# BD4Gv1.net
KiCad netlist of a schematic drawn in Altium Designer
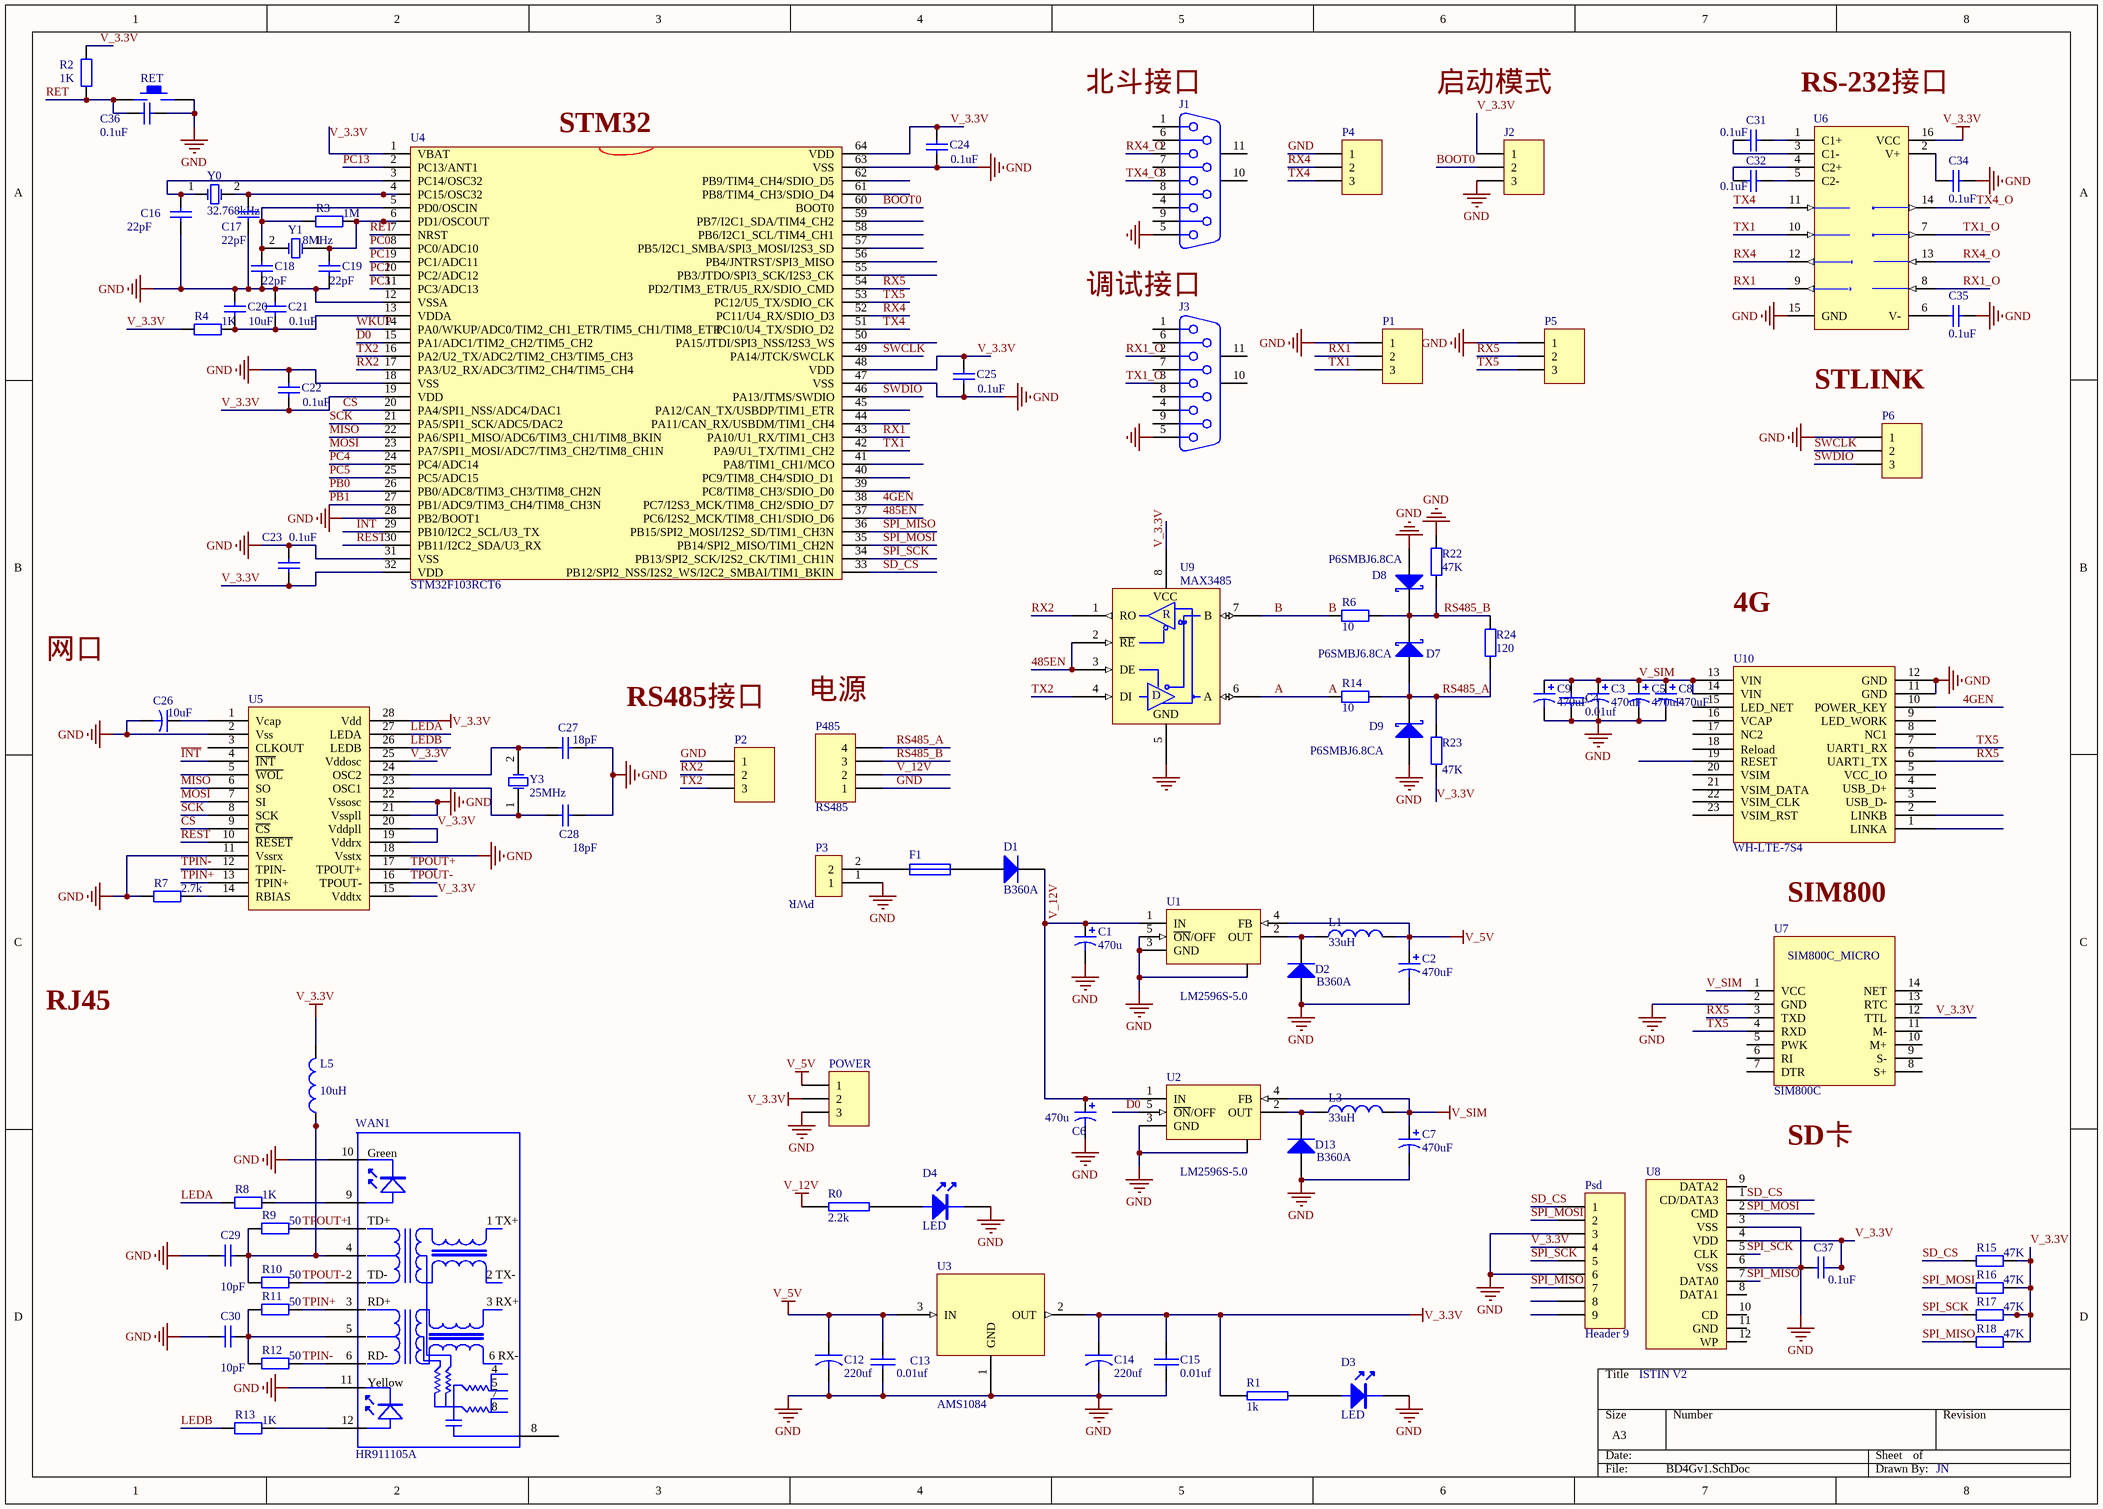
[diagram p0: BD4Gv1.SchDoc]

(export (version "E")
  (design (tool "Eeschema 10.0.6"))
  (components
    (comp (ref "C1")
      (value "470u")
      (footprint "C1007")
      (description "Polarized Capacitor (Surface Mount)")
      (fields (field (name "Comment") "470u/35V"))
      (libsource (lib "Miscellaneous Devices") (part "Cap Pol3"))
    )
    (comp (ref "C2")
      (value "470uF")
      (footprint "SMC")
      (description "Polarized Capacitor (Surface Mount)")
      (fields (field (name "Comment") "470u/10V"))
      (libsource (lib "Miscellaneous Devices") (part "Cap Pol3"))
    )
    (comp (ref "C3")
      (value "470uF")
      (footprint "SMC")
      (description "Polarized Capacitor (Surface Mount)")
      (fields (field (name "Comment") "470u/10V"))
      (libsource (lib "Miscellaneous Devices") (part "Cap Pol3"))
    )
    (comp (ref "C4")
      (value "0.01uf")
      (footprint "0805")
      (description "Capacitor")
      (libsource (lib "*") (part "CAP"))
    )
    (comp (ref "C5")
      (value "470uF")
      (footprint "SMC")
      (description "Polarized Capacitor (Surface Mount)")
      (fields (field (name "Comment") "470u/10V"))
      (libsource (lib "Miscellaneous Devices") (part "Cap Pol3"))
    )
    (comp (ref "C6")
      (value "470u")
      (footprint "C1007")
      (description "Polarized Capacitor (Surface Mount)")
      (fields (field (name "Comment") "470u/35V"))
      (libsource (lib "Miscellaneous Devices") (part "Cap Pol3"))
    )
    (comp (ref "C7")
      (value "470uF")
      (footprint "SMC")
      (description "Polarized Capacitor (Surface Mount)")
      (fields (field (name "Comment") "470u/10V"))
      (libsource (lib "Miscellaneous Devices") (part "Cap Pol3"))
    )
    (comp (ref "C8")
      (value "470uF")
      (footprint "SMC")
      (description "Polarized Capacitor (Surface Mount)")
      (fields (field (name "Comment") "470u/10V"))
      (libsource (lib "Miscellaneous Devices") (part "Cap Pol3"))
    )
    (comp (ref "C9")
      (value "470uF")
      (footprint "CC6.56.5")
      (description "Polarized Capacitor (Surface Mount)")
      (fields (field (name "Comment") "470u/10V"))
      (libsource (lib "Miscellaneous Devices") (part "Cap Pol3"))
    )
    (comp (ref "C12")
      (value "220uf")
      (footprint "SMC")
      (description "Capacitor")
      (libsource (lib "*") (part "CAPACITOR"))
    )
    (comp (ref "C13")
      (value "0.01uf")
      (footprint "0805")
      (description "Capacitor")
      (libsource (lib "*") (part "CAP"))
    )
    (comp (ref "C14")
      (value "220uf")
      (footprint "SMC")
      (description "Capacitor")
      (libsource (lib "*") (part "CAPACITOR"))
    )
    (comp (ref "C15")
      (value "0.01uf")
      (footprint "0805")
      (description "Capacitor")
      (libsource (lib "*") (part "CAP"))
    )
    (comp (ref "C16")
      (value "22pF")
      (footprint "0805")
      (description "Capacitor")
      (libsource (lib "Miscellaneous Devices") (part "Cap"))
    )
    (comp (ref "C17")
      (value "22pF")
      (footprint "0805")
      (description "Capacitor")
      (libsource (lib "Miscellaneous Devices") (part "Cap"))
    )
    (comp (ref "C18")
      (value "22pF")
      (footprint "0805")
      (description "Capacitor")
      (libsource (lib "Miscellaneous Devices") (part "Cap"))
    )
    (comp (ref "C19")
      (value "22pF")
      (footprint "0805")
      (description "Capacitor")
      (libsource (lib "Miscellaneous Devices") (part "Cap"))
    )
    (comp (ref "C20")
      (value "10uF")
      (footprint "0805")
      (description "Capacitor")
      (libsource (lib "Miscellaneous Devices") (part "Cap"))
    )
    (comp (ref "C21")
      (value "0.1uF")
      (footprint "0805")
      (description "Capacitor")
      (libsource (lib "Miscellaneous Devices") (part "Cap"))
    )
    (comp (ref "C22")
      (value "0.1uF")
      (footprint "0805")
      (description "Capacitor")
      (libsource (lib "Miscellaneous Devices") (part "Cap"))
    )
    (comp (ref "C23")
      (value "0.1uF")
      (footprint "0805")
      (description "Capacitor")
      (libsource (lib "Miscellaneous Devices") (part "Cap"))
    )
    (comp (ref "C24")
      (value "0.1uF")
      (footprint "0805")
      (description "Capacitor")
      (libsource (lib "Miscellaneous Devices") (part "Cap"))
    )
    (comp (ref "C25")
      (value "0.1uF")
      (footprint "0805")
      (description "Capacitor")
      (libsource (lib "Miscellaneous Devices") (part "Cap"))
    )
    (comp (ref "C26")
      (value "10uF")
      (footprint "0805")
      (description "Capacitor")
      (libsource (lib "Miscellaneous Devices") (part "Cap2"))
    )
    (comp (ref "C27")
      (value "18pF")
      (footprint "0805")
      (description "Capacitor")
      (libsource (lib "Miscellaneous Devices") (part "Cap"))
    )
    (comp (ref "C28")
      (value "18pF")
      (footprint "0805")
      (description "Capacitor")
      (libsource (lib "Miscellaneous Devices") (part "Cap"))
    )
    (comp (ref "C29")
      (value "10pF")
      (footprint "0805")
      (description "Capacitor")
      (libsource (lib "Miscellaneous Devices") (part "Cap"))
    )
    (comp (ref "C30")
      (value "10pF")
      (footprint "0805")
      (description "Capacitor")
      (libsource (lib "Miscellaneous Devices") (part "Cap"))
    )
    (comp (ref "C31")
      (value "0.1uF")
      (footprint "0805")
      (description "Capacitor")
      (libsource (lib "HLK-RM04_KIT-V2.3") (part "Cap"))
    )
    (comp (ref "C32")
      (value "0.1uF")
      (footprint "0805")
      (description "Capacitor")
      (libsource (lib "HLK-RM04_KIT-V2.3") (part "Cap"))
    )
    (comp (ref "C34")
      (value "0.1uF")
      (footprint "0805")
      (description "Capacitor")
      (libsource (lib "HLK-RM04_KIT-V2.3") (part "Cap"))
    )
    (comp (ref "C35")
      (value "0.1uF")
      (footprint "0805")
      (description "Capacitor")
      (libsource (lib "HLK-RM04_KIT-V2.3") (part "Cap"))
    )
    (comp (ref "C36")
      (value "0.1uF")
      (footprint "0805")
      (description "Capacitor")
      (libsource (lib "Miscellaneous Devices") (part "Cap"))
    )
    (comp (ref "C37")
      (value "0.1uF")
      (footprint "0805")
      (description "Capacitor")
      (libsource (lib "Miscellaneous Devices") (part "Cap"))
    )
    (comp (ref "D1")
      (value "B360A")
      (footprint "B360A")
      (description "Default Diode")
      (libsource (lib "Miscellaneous Devices") (part "Diode"))
    )
    (comp (ref "D2")
      (value "B360A")
      (footprint "B360A")
      (description "Default Diode")
      (libsource (lib "Miscellaneous Devices") (part "Diode"))
    )
    (comp (ref "D3") (value "LED") (footprint "LED_side") (libsource (lib "*") (part "LED")))
    (comp (ref "D4") (value "LED") (footprint "LED_side") (libsource (lib "*") (part "LED")))
    (comp (ref "D7")
      (value "P6SMBJ6.8CA")
      (footprint "DO-2144AA")
      (description "Schottky Diode")
      (libsource (lib "Miscellaneous Devices") (part "D Schottky"))
    )
    (comp (ref "D8")
      (value "P6SMBJ6.8CA")
      (footprint "DO-2144AA")
      (description "Schottky Diode")
      (libsource (lib "Miscellaneous Devices") (part "D Schottky"))
    )
    (comp (ref "D9")
      (value "P6SMBJ6.8CA")
      (footprint "DO-2144AA")
      (description "Schottky Diode")
      (libsource (lib "Miscellaneous Devices") (part "D Schottky"))
    )
    (comp (ref "D13")
      (value "B360A")
      (footprint "B360A")
      (description "Default Diode")
      (libsource (lib "Miscellaneous Devices") (part "Diode"))
    )
    (comp (ref "F1")
      (value "保险丝")
      (footprint "1812")
      (description "Fuse")
      (libsource (lib "Miscellaneous Devices") (part "Fuse 1"))
    )
    (comp (ref "J1")
      (value "D Connector 9")
      (footprint "DB9P")
      (description "Receptacle Assembly, 9 Position, Right Angle")
      (libsource (lib "Miscellaneous Connectors") (part "D Connector 9"))
    )
    (comp (ref "J2")
      (value "boot")
      (footprint "HDR1X3")
      (description "Header, 3-Pin")
      (libsource (lib "hete") (part "Header 3"))
    )
    (comp (ref "J3")
      (value "D Connector 9")
      (footprint "DB9P")
      (description "Receptacle Assembly, 9 Position, Right Angle")
      (libsource (lib "Miscellaneous Connectors") (part "D Connector 9"))
    )
    (comp (ref "L1")
      (value "33uH")
      (footprint "L0630")
      (description "Inductor,3A")
      (libsource (lib "Miscellaneous Devices") (part "Inductor"))
    )
    (comp (ref "L3")
      (value "33uH")
      (footprint "L0630")
      (description "Inductor,3A")
      (libsource (lib "Miscellaneous Devices") (part "Inductor"))
    )
    (comp (ref "L5")
      (value "10uH")
      (footprint "0805")
      (description "Inductor")
      (libsource (lib "Miscellaneous Devices") (part "Inductor"))
    )
    (comp (ref "P1")
      (value "UART")
      (footprint "HDR1X3")
      (description "Header, 3-Pin")
      (libsource (lib "Miscellaneous Connectors") (part "Header 3"))
    )
    (comp (ref "P2")
      (value "BD-TEST")
      (footprint "HDR1X3")
      (description "Header, 3-Pin")
      (libsource (lib "Miscellaneous Connectors") (part "MHDR1X3"))
    )
    (comp (ref "P3") (value "~") (footprint "H2_5.08_side") (libsource (lib "BD") (part "PWR")))
    (comp (ref "P4")
      (value "BD-TEST")
      (footprint "HDR1X3")
      (description "Header, 3-Pin")
      (libsource (lib "Miscellaneous Connectors") (part "MHDR1X3"))
    )
    (comp (ref "P5")
      (value "UART")
      (footprint "HDR1X3")
      (description "Header, 3-Pin")
      (libsource (lib "Miscellaneous Connectors") (part "Header 3"))
    )
    (comp (ref "P6")
      (value "STLINK")
      (footprint "HDR1X3")
      (description "Header, 3-Pin")
      (libsource (lib "Miscellaneous Connectors") (part "Header 3"))
    )
    (comp (ref "P485")
      (value "RS485")
      (footprint "H4_3.81")
      (description "Header, 4-Pin")
      (libsource (lib "Miscellaneous Connectors") (part "Header 4"))
    )
    (comp (ref "POWER")
      (value "UART")
      (footprint "HDR1X3")
      (description "Header, 3-Pin")
      (libsource (lib "Miscellaneous Connectors") (part "Header 3"))
    )
    (comp (ref "Psd")
      (value "Header 9")
      (footprint "HDR1X9")
      (description "Header, 9-Pin")
      (libsource (lib "Miscellaneous Connectors") (part "Header 9"))
    )
    (comp (ref "R0") (value "2.2k") (footprint "0805") (libsource (lib "*") (part "RES2")))
    (comp (ref "R1") (value "1k") (footprint "0805") (libsource (lib "*") (part "RES2")))
    (comp (ref "R2")
      (value "1K")
      (footprint "0805")
      (description "Resistor")
      (fields (field (name "Comment") "1k"))
      (libsource (lib "") (part "Res2_2"))
    )
    (comp (ref "R3")
      (value "1M")
      (footprint "0805")
      (description "Resistor")
      (libsource (lib "Miscellaneous Devices") (part "Res2"))
    )
    (comp (ref "R4")
      (value "1K")
      (footprint "0805")
      (description "Resistor")
      (fields (field (name "Comment") "1k"))
      (libsource (lib "Miscellaneous Devices") (part "Res2"))
    )
    (comp (ref "R6")
      (value "10")
      (footprint "0805")
      (description "Resistor")
      (libsource (lib "Miscellaneous Devices") (part "Res2"))
    )
    (comp (ref "R7")
      (value "2.7k")
      (footprint "0805")
      (description "Resistor")
      (libsource (lib "Miscellaneous Devices") (part "Res2"))
    )
    (comp (ref "R8")
      (value "1K")
      (footprint "0805")
      (description "Resistor")
      (fields (field (name "Comment") "1k"))
      (libsource (lib "Miscellaneous Devices") (part "Res2"))
    )
    (comp (ref "R9")
      (value "50")
      (footprint "0805")
      (description "Resistor")
      (libsource (lib "Miscellaneous Devices") (part "Res2"))
    )
    (comp (ref "R10")
      (value "50")
      (footprint "0805")
      (description "Resistor")
      (libsource (lib "Miscellaneous Devices") (part "Res2"))
    )
    (comp (ref "R11")
      (value "50")
      (footprint "0805")
      (description "Resistor")
      (libsource (lib "Miscellaneous Devices") (part "Res2"))
    )
    (comp (ref "R12")
      (value "50")
      (footprint "0805")
      (description "Resistor")
      (libsource (lib "Miscellaneous Devices") (part "Res2"))
    )
    (comp (ref "R13")
      (value "1K")
      (footprint "0805")
      (description "Resistor")
      (fields (field (name "Comment") "1k"))
      (libsource (lib "Miscellaneous Devices") (part "Res2"))
    )
    (comp (ref "R14")
      (value "10")
      (footprint "0805")
      (description "Resistor")
      (libsource (lib "Miscellaneous Devices") (part "Res2"))
    )
    (comp (ref "R15")
      (value "47K")
      (footprint "0805")
      (description "Resistor")
      (fields (field (name "Comment") "47k"))
      (libsource (lib "Miscellaneous Devices") (part "Res2"))
    )
    (comp (ref "R16")
      (value "47K")
      (footprint "0805")
      (description "Resistor")
      (fields (field (name "Comment") "47k"))
      (libsource (lib "Miscellaneous Devices") (part "Res2"))
    )
    (comp (ref "R17")
      (value "47K")
      (footprint "0805")
      (description "Resistor")
      (fields (field (name "Comment") "47k"))
      (libsource (lib "Miscellaneous Devices") (part "Res2"))
    )
    (comp (ref "R18")
      (value "47K")
      (footprint "0805")
      (description "Resistor")
      (fields (field (name "Comment") "47k"))
      (libsource (lib "Miscellaneous Devices") (part "Res2"))
    )
    (comp (ref "R22")
      (value "47K")
      (footprint "0805")
      (description "Resistor")
      (libsource (lib "") (part "Res2_1"))
    )
    (comp (ref "R23")
      (value "47K")
      (footprint "0805")
      (description "Resistor")
      (libsource (lib "") (part "Res2_1"))
    )
    (comp (ref "R24")
      (value "120")
      (footprint "0805")
      (description "Resistor")
      (libsource (lib "") (part "Res2_1"))
    )
    (comp (ref "RET") (value "KEY_M") (footprint "KEY_90") (libsource (lib "MiniSTM32底板_SCH") (part "KEY_M")))
    (comp (ref "U1")
      (value "LM2596S-5.0")
      (footprint "936A-02")
      (description "5V稳压芯片")
      (libsource (lib "fszhang") (part "LM2596S-5.0"))
    )
    (comp (ref "U2")
      (value "LM2596S-5.0")
      (footprint "936A-02")
      (description "5V稳压芯片")
      (libsource (lib "fszhang") (part "LM2596S-5.0"))
    )
    (comp (ref "U3") (value "AMS1084") (footprint "TO-252") (libsource (lib "Sheet1") (part "AMS117")))
    (comp (ref "U4")
      (value "STM32F103RCT6")
      (footprint "LQFP64_N")
      (libsource (lib "MiniSTM32 V3.0封装库") (part "STM32F103RDT6"))
    )
    (comp (ref "U5") (value "EN28J60") (footprint "SSOP28") (libsource (lib "PN532") (part "EN28J60")))
    (comp (ref "U6")
      (value "MAX3232ESE")
      (footprint "NSO16_N")
      (description "3.0V TO 5.5V, Low-Power, up to 1Mbps, True RS-232 Transceiver Using Four 0.1µF External Capacitor")
      (libsource (lib "Maxim Communication Transceiver") (part "MAX3232ESE"))
    )
    (comp (ref "U7")
      (value "SIM800C")
      (footprint "PCBComponent_1")
      (libsource (lib "SIM800C_MICRO") (part "Component_1"))
    )
    (comp (ref "U8")
      (value "sd card")
      (footprint "MICRO-SD")
      (libsource (lib "MiniSTM32 V3.0封装库") (part "sd card"))
    )
    (comp (ref "U9") (value "MAX3485") (footprint "NSO8_M") (libsource (lib "*") (part "MAX1487E")))
    (comp (ref "U10")
      (value "WH-LTE-7S4")
      (footprint "WH-LTE-7S4")
      (libsource (lib "BD4Gv1") (part "WH-LTE-7S4"))
    )
    (comp (ref "WAN1")
      (value "HR911105A")
      (footprint "HR911105A")
      (libsource (lib "V2-Project") (part "HR911105A"))
    )
    (comp (ref "Y0")
      (value "32.768kHz")
      (footprint "XTAL-B")
      (description "Crystal Oscillator")
      (libsource (lib "MiniSTM32 V3.0封装库") (part "XTAL"))
    )
    (comp (ref "Y1")
      (value "8MHz")
      (footprint "贴片晶振")
      (description "Crystal Oscillator")
      (libsource (lib "MiniSTM32 V3.0封装库") (part "XTAL"))
    )
    (comp (ref "Y3")
      (value "25MHz")
      (footprint "4P-Crystal")
      (description "Crystal Oscillator")
      (libsource (lib "Miscellaneous Devices") (part "XTAL"))
    )
  )
  (nets
    (net (code "1") (name "/4GEN") (class "Default")
      (node (ref "U10") (pin "10") (pinfunction "POWER_KEY_10") (pintype "passive"))
      (node (ref "U4") (pin "38") (pinfunction "PC7/I2S3_MCK/TIM8_CH2/SDIO_D7_38") (pintype "passive"))
    )
    (net (code "2") (name "/485EN") (class "Default")
      (node (ref "U4") (pin "37") (pinfunction "PC6/I2S2_MCK/TIM8_CH1/SDIO_D6_37") (pintype "passive"))
      (node (ref "U9") (pin "2") (pinfunction "~{RE}_2") (pintype "input"))
      (node (ref "U9") (pin "3") (pinfunction "DE_3") (pintype "input"))
    )
    (net (code "3") (name "/A") (class "Default")
      (node (ref "R14") (pin "1") (pinfunction "1_1") (pintype "passive"))
      (node (ref "U9") (pin "6") (pinfunction "A_6") (pintype "bidirectional"))
    )
    (net (code "4") (name "/B") (class "Default")
      (node (ref "R6") (pin "1") (pinfunction "1_1") (pintype "passive"))
      (node (ref "U9") (pin "7") (pinfunction "B_7") (pintype "bidirectional"))
    )
    (net (code "5") (name "/BOOT0") (class "Default")
      (node (ref "J2") (pin "2") (pinfunction "2_2") (pintype "passive"))
      (node (ref "U4") (pin "60") (pinfunction "BOOT0_60") (pintype "passive"))
    )
    (net (code "6") (name "/D0") (class "Default")
      (node (ref "U2") (pin "5") (pinfunction "~{ON}/OFF_5") (pintype "input"))
      (node (ref "U4") (pin "15") (pinfunction "PA1/ADC1/TIM2_CH2/TIM5_CH2_15") (pintype "passive"))
    )
    (net (code "7") (name "/LEDA") (class "Default")
      (node (ref "R8") (pin "1") (pinfunction "1_1") (pintype "passive"))
      (node (ref "U5") (pin "27") (pinfunction "LEDA_27") (pintype "passive"))
    )
    (net (code "8") (name "/LEDB") (class "Default")
      (node (ref "R13") (pin "1") (pinfunction "1_1") (pintype "passive"))
      (node (ref "U5") (pin "26") (pinfunction "LEDB_26") (pintype "passive"))
    )
    (net (code "9") (name "/MISO") (class "Default")
      (node (ref "U4") (pin "22") (pinfunction "PA6/SPI1_MISO/ADC6/TIM3_CH1/TIM8_BKIN_22") (pintype "passive"))
      (node (ref "U5") (pin "6") (pinfunction "SO_6") (pintype "passive"))
    )
    (net (code "10") (name "/MOSI") (class "Default")
      (node (ref "U4") (pin "23") (pinfunction "PA7/SPI1_MOSI/ADC7/TIM3_CH2/TIM8_CH1N_23") (pintype "passive"))
      (node (ref "U5") (pin "7") (pinfunction "SI_7") (pintype "passive"))
    )
    (net (code "11") (name "/PB0") (class "Default")
      (node (ref "U4") (pin "26") (pinfunction "PB0/ADC8/TIM3_CH3/TIM8_CH2N_26") (pintype "passive"))
    )
    (net (code "12") (name "/PB1") (class "Default")
      (node (ref "U4") (pin "27") (pinfunction "PB1/ADC9/TIM3_CH4/TIM8_CH3N_27") (pintype "passive"))
    )
    (net (code "13") (name "/PC0") (class "Default")
      (node (ref "U4") (pin "8") (pinfunction "PC0/ADC10_8") (pintype "passive"))
    )
    (net (code "14") (name "/PC1") (class "Default")
      (node (ref "U4") (pin "9") (pinfunction "PC1/ADC11_9") (pintype "passive"))
    )
    (net (code "15") (name "/PC2") (class "Default")
      (node (ref "U4") (pin "10") (pinfunction "PC2/ADC12_10") (pintype "passive"))
    )
    (net (code "16") (name "/PC3") (class "Default")
      (node (ref "U4") (pin "11") (pinfunction "PC3/ADC13_11") (pintype "passive"))
    )
    (net (code "17") (name "/PC4") (class "Default")
      (node (ref "U4") (pin "24") (pinfunction "PC4/ADC14_24") (pintype "passive"))
    )
    (net (code "18") (name "/PC5") (class "Default")
      (node (ref "U4") (pin "25") (pinfunction "PC5/ADC15_25") (pintype "passive"))
    )
    (net (code "19") (name "/PC13") (class "Default")
      (node (ref "U4") (pin "2") (pinfunction "PC13/ANT1_2") (pintype "passive"))
    )
    (net (code "20") (name "/REST") (class "Default")
      (node (ref "U4") (pin "30") (pinfunction "PB11/I2C2_SDA/U3_RX_30") (pintype "passive"))
      (node (ref "U5") (pin "10") (pinfunction "~{RESET}_10") (pintype "passive"))
    )
    (net (code "21") (name "/RET") (class "Default")
      (node (ref "C36") (pin "1") (pinfunction "1_1") (pintype "passive"))
      (node (ref "R2") (pin "1") (pinfunction "1_1") (pintype "passive"))
      (node (ref "RET") (pin "1") (pinfunction "1_1") (pintype "passive"))
      (node (ref "U4") (pin "7") (pinfunction "NRST_7") (pintype "passive"))
    )
    (net (code "22") (name "/RS485_A") (class "Default")
      (node (ref "D7") (pin "1") (pinfunction "A_1") (pintype "passive"))
      (node (ref "D9") (pin "2") (pinfunction "K_2") (pintype "passive"))
      (node (ref "P485") (pin "4") (pinfunction "4_4") (pintype "passive"))
      (node (ref "R14") (pin "2") (pinfunction "2_2") (pintype "passive"))
      (node (ref "R23") (pin "1") (pinfunction "1_1") (pintype "passive"))
      (node (ref "R24") (pin "2") (pinfunction "2_2") (pintype "passive"))
    )
    (net (code "23") (name "/RS485_B") (class "Default")
      (node (ref "D7") (pin "2") (pinfunction "K_2") (pintype "passive"))
      (node (ref "D8") (pin "2") (pinfunction "K_2") (pintype "passive"))
      (node (ref "P485") (pin "3") (pinfunction "3_3") (pintype "passive"))
      (node (ref "R22") (pin "2") (pinfunction "2_2") (pintype "passive"))
      (node (ref "R24") (pin "1") (pinfunction "1_1") (pintype "passive"))
      (node (ref "R6") (pin "2") (pinfunction "2_2") (pintype "passive"))
    )
    (net (code "24") (name "/RX1") (class "Default")
      (node (ref "P1") (pin "2") (pinfunction "2_2") (pintype "passive"))
      (node (ref "U4") (pin "43") (pinfunction "PA10/U1_RX/TIM1_CH3_43") (pintype "passive"))
      (node (ref "U6") (pin "9") (pinfunction "R2OUT_9") (pintype "output"))
    )
    (net (code "25") (name "/RX1_O") (class "Default")
      (node (ref "J3") (pin "2") (pinfunction "2_2") (pintype "passive"))
      (node (ref "U6") (pin "8") (pinfunction "R2IN_8") (pintype "input"))
    )
    (net (code "26") (name "/RX2") (class "Default")
      (node (ref "P2") (pin "2") (pinfunction "2_2") (pintype "passive"))
      (node (ref "U4") (pin "17") (pinfunction "PA3/U2_RX/ADC3/TIM2_CH4/TIM5_CH4_17") (pintype "passive"))
      (node (ref "U9") (pin "1") (pinfunction "RO_1") (pintype "output"))
    )
    (net (code "27") (name "/RX4") (class "Default")
      (node (ref "P4") (pin "2") (pinfunction "2_2") (pintype "passive"))
      (node (ref "U4") (pin "52") (pinfunction "PC11/U4_RX/SDIO_D3_52") (pintype "passive"))
      (node (ref "U6") (pin "12") (pinfunction "R1OUT_12") (pintype "output"))
    )
    (net (code "28") (name "/RX4_O") (class "Default")
      (node (ref "J1") (pin "2") (pinfunction "2_2") (pintype "passive"))
      (node (ref "U6") (pin "13") (pinfunction "R1IN_13") (pintype "input"))
    )
    (net (code "29") (name "/RX5") (class "Default")
      (node (ref "P5") (pin "2") (pinfunction "2_2") (pintype "passive"))
      (node (ref "U10") (pin "6") (pinfunction "UART1_TX_6") (pintype "passive"))
      (node (ref "U4") (pin "54") (pinfunction "PD2/TIM3_ETR/U5_RX/SDIO_CMD_54") (pintype "passive"))
      (node (ref "U7") (pin "3") (pinfunction "TXD_3") (pintype "passive"))
    )
    (net (code "30") (name "/SCK") (class "Default")
      (node (ref "U4") (pin "21") (pinfunction "PA5/SPI1_SCK/ADC5/DAC2_21") (pintype "passive"))
      (node (ref "U5") (pin "8") (pinfunction "SCK_8") (pintype "passive"))
    )
    (net (code "31") (name "/SD_CS") (class "Default")
      (node (ref "Psd") (pin "1") (pinfunction "1_1") (pintype "passive"))
      (node (ref "R15") (pin "1") (pinfunction "1_1") (pintype "passive"))
      (node (ref "U4") (pin "33") (pinfunction "PB12/SPI2_NSS/I2S2_WS/I2C2_SMBAI/TIM1_BKIN_33") (pintype "passive"))
      (node (ref "U8") (pin "1") (pinfunction "CD/DATA3_1") (pintype "passive"))
    )
    (net (code "34") (name "/SPI_MISO") (class "Default")
      (node (ref "Psd") (pin "7") (pinfunction "7_7") (pintype "passive"))
      (node (ref "R18") (pin "1") (pinfunction "1_1") (pintype "passive"))
      (node (ref "U4") (pin "36") (pinfunction "PB15/SPI2_MOSI/I2S2_SD/TIM1_CH3N_36") (pintype "passive"))
      (node (ref "U8") (pin "7") (pinfunction "DATA0_7") (pintype "passive"))
    )
    (net (code "35") (name "/SPI_MOSI") (class "Default")
      (node (ref "Psd") (pin "2") (pinfunction "2_2") (pintype "passive"))
      (node (ref "R16") (pin "1") (pinfunction "1_1") (pintype "passive"))
      (node (ref "U4") (pin "35") (pinfunction "PB14/SPI2_MISO/TIM1_CH2N_35") (pintype "passive"))
      (node (ref "U8") (pin "2") (pinfunction "CMD_2") (pintype "passive"))
    )
    (net (code "36") (name "/SPI_SCK") (class "Default")
      (node (ref "Psd") (pin "5") (pinfunction "5_5") (pintype "passive"))
      (node (ref "R17") (pin "1") (pinfunction "1_1") (pintype "passive"))
      (node (ref "U4") (pin "34") (pinfunction "PB13/SPI2_SCK/I2S2_CK/TIM1_CH1N_34") (pintype "passive"))
      (node (ref "U8") (pin "5") (pinfunction "CLK_5") (pintype "passive"))
    )
    (net (code "38") (name "/SWCLK") (class "Default")
      (node (ref "P6") (pin "2") (pinfunction "2_2") (pintype "passive"))
      (node (ref "U4") (pin "49") (pinfunction "PA14/JTCK/SWCLK_49") (pintype "passive"))
    )
    (net (code "39") (name "/SWDIO") (class "Default")
      (node (ref "P6") (pin "3") (pinfunction "3_3") (pintype "passive"))
      (node (ref "U4") (pin "46") (pinfunction "PA13/JTMS/SWDIO_46") (pintype "passive"))
    )
    (net (code "40") (name "/TPIN+") (class "Default")
      (node (ref "R11") (pin "2") (pinfunction "2_2") (pintype "passive"))
      (node (ref "U5") (pin "13") (pinfunction "TPIN+_13") (pintype "passive"))
      (node (ref "WAN1") (pin "3") (pintype "passive"))
    )
    (net (code "41") (name "/TPIN-") (class "Default")
      (node (ref "R12") (pin "2") (pinfunction "2_2") (pintype "passive"))
      (node (ref "U5") (pin "12") (pinfunction "TPIN-_12") (pintype "passive"))
      (node (ref "WAN1") (pin "6") (pintype "passive"))
    )
    (net (code "42") (name "/TPOUT+") (class "Default")
      (node (ref "R9") (pin "2") (pinfunction "2_2") (pintype "passive"))
      (node (ref "U5") (pin "17") (pinfunction "TPOUT+_17") (pintype "passive"))
      (node (ref "WAN1") (pin "1") (pintype "passive"))
    )
    (net (code "43") (name "/TPOUT-") (class "Default")
      (node (ref "R10") (pin "2") (pinfunction "2_2") (pintype "passive"))
      (node (ref "U5") (pin "16") (pinfunction "TPOUT-_16") (pintype "passive"))
      (node (ref "WAN1") (pin "2") (pintype "passive"))
    )
    (net (code "44") (name "/TX1") (class "Default")
      (node (ref "P1") (pin "3") (pinfunction "3_3") (pintype "passive"))
      (node (ref "U4") (pin "42") (pinfunction "PA9/U1_TX/TIM1_CH2_42") (pintype "passive"))
      (node (ref "U6") (pin "10") (pinfunction "T2IN_10") (pintype "input"))
    )
    (net (code "45") (name "/TX1_O") (class "Default")
      (node (ref "J3") (pin "3") (pinfunction "3_3") (pintype "passive"))
      (node (ref "U6") (pin "7") (pinfunction "T2OUT_7") (pintype "output"))
    )
    (net (code "46") (name "/TX2") (class "Default")
      (node (ref "P2") (pin "3") (pinfunction "3_3") (pintype "passive"))
      (node (ref "U4") (pin "16") (pinfunction "PA2/U2_TX/ADC2/TIM2_CH3/TIM5_CH3_16") (pintype "passive"))
      (node (ref "U9") (pin "4") (pinfunction "DI_4") (pintype "input"))
    )
    (net (code "47") (name "/TX4") (class "Default")
      (node (ref "P4") (pin "3") (pinfunction "3_3") (pintype "passive"))
      (node (ref "U4") (pin "51") (pinfunction "PC10/U4_TX/SDIO_D2_51") (pintype "passive"))
      (node (ref "U6") (pin "11") (pinfunction "T1IN_11") (pintype "input"))
    )
    (net (code "48") (name "/TX4_O") (class "Default")
      (node (ref "J1") (pin "3") (pinfunction "3_3") (pintype "passive"))
      (node (ref "U6") (pin "14") (pinfunction "T1OUT_14") (pintype "output"))
    )
    (net (code "49") (name "/TX5") (class "Default")
      (node (ref "P5") (pin "3") (pinfunction "3_3") (pintype "passive"))
      (node (ref "U10") (pin "7") (pinfunction "UART1_RX_7") (pintype "passive"))
      (node (ref "U4") (pin "53") (pinfunction "PC12/U5_TX/SDIO_CK_53") (pintype "passive"))
      (node (ref "U7") (pin "4") (pinfunction "RXD_4") (pintype "passive"))
    )
    (net (code "50") (name "/WKUP") (class "Default")
      (node (ref "U4") (pin "14") (pinfunction "PA0/WKUP/ADC0/TIM2_CH1_ETR/TIM5_CH1/TIM8_ETR_14") (pintype "passive"))
    )
    (net (code "51") (name "/~{CS}") (class "Default")
      (node (ref "U4") (pin "20") (pinfunction "PA4/SPI1_NSS/ADC4/DAC1_20") (pintype "passive"))
      (node (ref "U5") (pin "9") (pinfunction "~{CS}_9") (pintype "passive"))
    )
    (net (code "52") (name "/~{INT}") (class "Default")
      (node (ref "U4") (pin "29") (pinfunction "PB10/I2C2_SCL/U3_TX_29") (pintype "passive"))
      (node (ref "U5") (pin "4") (pinfunction "~{INT}_4") (pintype "passive"))
    )
    (net (code "55") (name "GND") (class "Default")
      (node (ref "C1") (pin "2") (pinfunction "2_2") (pintype "passive"))
      (node (ref "C12") (pin "2") (pinfunction "2_2") (pintype "passive"))
      (node (ref "C13") (pin "2") (pinfunction "2_2") (pintype "passive"))
      (node (ref "C14") (pin "2") (pinfunction "2_2") (pintype "passive"))
      (node (ref "C15") (pin "2") (pinfunction "2_2") (pintype "passive"))
      (node (ref "C16") (pin "1") (pinfunction "1_1") (pintype "passive"))
      (node (ref "C17") (pin "1") (pinfunction "1_1") (pintype "passive"))
      (node (ref "C18") (pin "1") (pinfunction "1_1") (pintype "passive"))
      (node (ref "C19") (pin "1") (pinfunction "1_1") (pintype "passive"))
      (node (ref "C2") (pin "2") (pinfunction "2_2") (pintype "passive"))
      (node (ref "C20") (pin "2") (pinfunction "2_2") (pintype "passive"))
      (node (ref "C21") (pin "1") (pinfunction "1_1") (pintype "passive"))
      (node (ref "C22") (pin "1") (pinfunction "1_1") (pintype "passive"))
      (node (ref "C23") (pin "1") (pinfunction "1_1") (pintype "passive"))
      (node (ref "C24") (pin "2") (pinfunction "2_2") (pintype "passive"))
      (node (ref "C25") (pin "2") (pinfunction "2_2") (pintype "passive"))
      (node (ref "C26") (pin "1") (pinfunction "1_1") (pintype "passive"))
      (node (ref "C27") (pin "2") (pinfunction "2_2") (pintype "passive"))
      (node (ref "C28") (pin "2") (pinfunction "2_2") (pintype "passive"))
      (node (ref "C29") (pin "1") (pinfunction "1_1") (pintype "passive"))
      (node (ref "C3") (pin "2") (pinfunction "2_2") (pintype "passive"))
      (node (ref "C30") (pin "1") (pinfunction "1_1") (pintype "passive"))
      (node (ref "C34") (pin "2") (pinfunction "2_2") (pintype "passive"))
      (node (ref "C35") (pin "2") (pinfunction "2_2") (pintype "passive"))
      (node (ref "C36") (pin "2") (pinfunction "2_2") (pintype "passive"))
      (node (ref "C37") (pin "2") (pinfunction "2_2") (pintype "passive"))
      (node (ref "C4") (pin "2") (pinfunction "2_2") (pintype "passive"))
      (node (ref "C5") (pin "2") (pinfunction "2_2") (pintype "passive"))
      (node (ref "C6") (pin "2") (pinfunction "2_2") (pintype "passive"))
      (node (ref "C7") (pin "2") (pinfunction "2_2") (pintype "passive"))
      (node (ref "C8") (pin "2") (pinfunction "2_2") (pintype "passive"))
      (node (ref "C9") (pin "2") (pinfunction "2_2") (pintype "passive"))
      (node (ref "D13") (pin "1") (pinfunction "A_1") (pintype "passive"))
      (node (ref "D2") (pin "1") (pinfunction "A_1") (pintype "passive"))
      (node (ref "D3") (pin "2") (pinfunction "2_2") (pintype "passive"))
      (node (ref "D4") (pin "2") (pinfunction "2_2") (pintype "passive"))
      (node (ref "D8") (pin "1") (pinfunction "A_1") (pintype "passive"))
      (node (ref "D9") (pin "1") (pinfunction "A_1") (pintype "passive"))
      (node (ref "J1") (pin "5") (pinfunction "5_5") (pintype "passive"))
      (node (ref "J2") (pin "3") (pinfunction "3_3") (pintype "passive"))
      (node (ref "J3") (pin "5") (pinfunction "5_5") (pintype "passive"))
      (node (ref "P1") (pin "1") (pinfunction "1_1") (pintype "passive"))
      (node (ref "P2") (pin "1") (pinfunction "1_1") (pintype "passive"))
      (node (ref "P3") (pin "1") (pinfunction "1_1") (pintype "passive"))
      (node (ref "P4") (pin "1") (pinfunction "1_1") (pintype "passive"))
      (node (ref "P485") (pin "1") (pinfunction "1_1") (pintype "passive"))
      (node (ref "P5") (pin "1") (pinfunction "1_1") (pintype "passive"))
      (node (ref "P6") (pin "1") (pinfunction "1_1") (pintype "passive"))
      (node (ref "POWER") (pin "3") (pinfunction "3_3") (pintype "passive"))
      (node (ref "Psd") (pin "3") (pinfunction "3_3") (pintype "passive"))
      (node (ref "Psd") (pin "6") (pinfunction "6_6") (pintype "passive"))
      (node (ref "R22") (pin "1") (pinfunction "1_1") (pintype "passive"))
      (node (ref "R7") (pin "1") (pinfunction "1_1") (pintype "passive"))
      (node (ref "RET") (pin "2") (pinfunction "2_2") (pintype "passive"))
      (node (ref "U1") (pin "3") (pinfunction "GND_3") (pintype "power_in"))
      (node (ref "U1") (pin "5") (pinfunction "~{ON}/OFF_5") (pintype "input"))
      (node (ref "U1") (pin "6") (pinfunction "6_6") (pintype "power_in"))
      (node (ref "U10") (pin "11") (pinfunction "GND_11") (pintype "passive"))
      (node (ref "U10") (pin "12") (pinfunction "GND_12") (pintype "passive"))
      (node (ref "U2") (pin "3") (pinfunction "GND_3") (pintype "power_in"))
      (node (ref "U2") (pin "6") (pinfunction "6_6") (pintype "power_in"))
      (node (ref "U3") (pin "1") (pinfunction "GND_1") (pintype "passive"))
      (node (ref "U4") (pin "12") (pinfunction "VSSA_12") (pintype "passive"))
      (node (ref "U4") (pin "18") (pinfunction "VSS_18") (pintype "passive"))
      (node (ref "U4") (pin "28") (pinfunction "PB2/BOOT1_28") (pintype "passive"))
      (node (ref "U4") (pin "31") (pinfunction "VSS_31") (pintype "passive"))
      (node (ref "U4") (pin "47") (pinfunction "VSS_47") (pintype "passive"))
      (node (ref "U4") (pin "63") (pinfunction "VSS_63") (pintype "passive"))
      (node (ref "U5") (pin "11") (pinfunction "Vssrx_11") (pintype "passive"))
      (node (ref "U5") (pin "18") (pinfunction "Vsstx_18") (pintype "passive"))
      (node (ref "U5") (pin "2") (pinfunction "Vss_2") (pintype "passive"))
      (node (ref "U5") (pin "21") (pinfunction "Vsspll_21") (pintype "passive"))
      (node (ref "U5") (pin "22") (pinfunction "Vssosc_22") (pintype "passive"))
      (node (ref "U6") (pin "15") (pinfunction "GND_15") (pintype "power_in"))
      (node (ref "U7") (pin "2") (pinfunction "GND_2") (pintype "passive"))
      (node (ref "U8") (pin "3") (pinfunction "VSS_3") (pintype "passive"))
      (node (ref "U8") (pin "6") (pinfunction "VSS_6") (pintype "passive"))
      (node (ref "U9") (pin "5") (pinfunction "GND_5") (pintype "power_in"))
      (node (ref "WAN1") (pin "10") (pintype "passive"))
      (node (ref "WAN1") (pin "11") (pintype "passive"))
    )
    (net (code "56") (name "Net-(C29-Pad2)") (class "Default")
      (node (ref "C29") (pin "2") (pinfunction "2_2") (pintype "passive"))
      (node (ref "L5") (pin "1") (pinfunction "1_1") (pintype "passive"))
      (node (ref "R10") (pin "1") (pinfunction "1_1") (pintype "passive"))
      (node (ref "R9") (pin "1") (pinfunction "1_1") (pintype "passive"))
      (node (ref "WAN1") (pin "4") (pintype "passive"))
    )
    (net (code "57") (name "Net-(C30-Pad2)") (class "Default")
      (node (ref "C30") (pin "2") (pinfunction "2_2") (pintype "passive"))
      (node (ref "R11") (pin "1") (pinfunction "1_1") (pintype "passive"))
      (node (ref "R12") (pin "1") (pinfunction "1_1") (pintype "passive"))
      (node (ref "WAN1") (pin "5") (pintype "passive"))
    )
    (net (code "58") (name "Net-(D1-A)") (class "Default")
      (node (ref "D1") (pin "1") (pinfunction "A_1") (pintype "passive"))
      (node (ref "F1") (pin "2") (pinfunction "2_2") (pintype "passive"))
    )
    (net (code "59") (name "Net-(D2-K)") (class "Default")
      (node (ref "D2") (pin "2") (pinfunction "K_2") (pintype "passive"))
      (node (ref "L1") (pin "1") (pinfunction "1_1") (pintype "passive"))
      (node (ref "U1") (pin "2") (pinfunction "OUT_2") (pintype "power_in"))
    )
    (net (code "60") (name "Net-(D3-Pad1)") (class "Default")
      (node (ref "D3") (pin "1") (pinfunction "1_1") (pintype "passive"))
      (node (ref "R1") (pin "1") (pinfunction "1_1") (pintype "passive"))
    )
    (net (code "61") (name "Net-(D4-Pad1)") (class "Default")
      (node (ref "D4") (pin "1") (pinfunction "1_1") (pintype "passive"))
      (node (ref "R0") (pin "1") (pinfunction "1_1") (pintype "passive"))
    )
    (net (code "62") (name "Net-(D13-K)") (class "Default")
      (node (ref "D13") (pin "2") (pinfunction "K_2") (pintype "passive"))
      (node (ref "L3") (pin "1") (pinfunction "1_1") (pintype "passive"))
      (node (ref "U2") (pin "2") (pinfunction "OUT_2") (pintype "power_in"))
    )
    (net (code "63") (name "Net-(F1-Pad1)") (class "Default")
      (node (ref "F1") (pin "1") (pinfunction "1_1") (pintype "passive"))
      (node (ref "P3") (pin "2") (pinfunction "2_2") (pintype "passive"))
    )
    (net (code "64") (name "Net-(R8-Pad2)") (class "Default")
      (node (ref "R8") (pin "2") (pinfunction "2_2") (pintype "passive"))
      (node (ref "WAN1") (pin "9") (pintype "passive"))
    )
    (net (code "65") (name "Net-(R13-Pad2)") (class "Default")
      (node (ref "R13") (pin "2") (pinfunction "2_2") (pintype "passive"))
      (node (ref "WAN1") (pin "12") (pintype "passive"))
    )
    (net (code "66") (name "Net-(U4-PC14{slash}OSC32)") (class "Default")
      (node (ref "C16") (pin "2") (pinfunction "2_2") (pintype "passive"))
      (node (ref "U4") (pin "3") (pinfunction "PC14/OSC32_3") (pintype "passive"))
      (node (ref "Y0") (pin "1") (pinfunction "OSC1_1") (pintype "passive"))
    )
    (net (code "67") (name "Net-(U4-PC15{slash}OSC32)") (class "Default")
      (node (ref "C17") (pin "2") (pinfunction "2_2") (pintype "passive"))
      (node (ref "U4") (pin "4") (pinfunction "PC15/OSC32_4") (pintype "passive"))
      (node (ref "Y0") (pin "2") (pinfunction "OSC2_2") (pintype "passive"))
    )
    (net (code "68") (name "Net-(U4-PD0{slash}OSCIN)") (class "Default")
      (node (ref "C18") (pin "2") (pinfunction "2_2") (pintype "passive"))
      (node (ref "R3") (pin "1") (pinfunction "1_1") (pintype "passive"))
      (node (ref "U4") (pin "5") (pinfunction "PD0/OSCIN_5") (pintype "passive"))
      (node (ref "Y1") (pin "2") (pinfunction "OSC2_2") (pintype "passive"))
    )
    (net (code "69") (name "Net-(U4-PD1{slash}OSCOUT)") (class "Default")
      (node (ref "C19") (pin "2") (pinfunction "2_2") (pintype "passive"))
      (node (ref "R3") (pin "2") (pinfunction "2_2") (pintype "passive"))
      (node (ref "U4") (pin "6") (pinfunction "PD1/OSCOUT_6") (pintype "passive"))
      (node (ref "Y1") (pin "1") (pinfunction "OSC1_1") (pintype "passive"))
    )
    (net (code "70") (name "Net-(U4-VDDA)") (class "Default")
      (node (ref "C20") (pin "1") (pinfunction "1_1") (pintype "passive"))
      (node (ref "C21") (pin "2") (pinfunction "2_2") (pintype "passive"))
      (node (ref "R4") (pin "2") (pinfunction "2_2") (pintype "passive"))
      (node (ref "U4") (pin "13") (pinfunction "VDDA_13") (pintype "passive"))
    )
    (net (code "71") (name "Net-(U5-OSC1)") (class "Default")
      (node (ref "C28") (pin "1") (pinfunction "1_1") (pintype "passive"))
      (node (ref "U5") (pin "23") (pinfunction "OSC1_23") (pintype "passive"))
      (node (ref "Y3") (pin "1") (pinfunction "OSC1_1") (pintype "passive"))
    )
    (net (code "72") (name "Net-(U5-OSC2)") (class "Default")
      (node (ref "C27") (pin "1") (pinfunction "1_1") (pintype "passive"))
      (node (ref "U5") (pin "24") (pinfunction "OSC2_24") (pintype "passive"))
      (node (ref "Y3") (pin "2") (pinfunction "OSC2_2") (pintype "passive"))
    )
    (net (code "73") (name "Net-(U5-RBIAS)") (class "Default")
      (node (ref "R7") (pin "2") (pinfunction "2_2") (pintype "passive"))
      (node (ref "U5") (pin "14") (pinfunction "RBIAS_14") (pintype "passive"))
    )
    (net (code "74") (name "Net-(U5-Vcap)") (class "Default")
      (node (ref "C26") (pin "2") (pinfunction "2_2") (pintype "passive"))
      (node (ref "U5") (pin "1") (pinfunction "Vcap_1") (pintype "passive"))
    )
    (net (code "75") (name "Net-(U6-C1+)") (class "Default")
      (node (ref "C31") (pin "2") (pinfunction "2_2") (pintype "passive"))
      (node (ref "U6") (pin "1") (pinfunction "C1+_1") (pintype "passive"))
    )
    (net (code "76") (name "Net-(U6-C1-)") (class "Default")
      (node (ref "C31") (pin "1") (pinfunction "1_1") (pintype "passive"))
      (node (ref "U6") (pin "3") (pinfunction "C1-_3") (pintype "passive"))
    )
    (net (code "77") (name "Net-(U6-C2+)") (class "Default")
      (node (ref "C32") (pin "1") (pinfunction "1_1") (pintype "passive"))
      (node (ref "U6") (pin "4") (pinfunction "C2+_4") (pintype "passive"))
    )
    (net (code "78") (name "Net-(U6-C2-)") (class "Default")
      (node (ref "C32") (pin "2") (pinfunction "2_2") (pintype "passive"))
      (node (ref "U6") (pin "5") (pinfunction "C2-_5") (pintype "passive"))
    )
    (net (code "79") (name "Net-(U6-V+)") (class "Default")
      (node (ref "C34") (pin "1") (pinfunction "1_1") (pintype "passive"))
      (node (ref "U6") (pin "2") (pinfunction "V+_2") (pintype "power_in"))
    )
    (net (code "80") (name "Net-(U6-V-)") (class "Default")
      (node (ref "C35") (pin "1") (pinfunction "1_1") (pintype "passive"))
      (node (ref "U6") (pin "6") (pinfunction "V-_6") (pintype "power_in"))
    )
    (net (code "81") (name "V_3.3V") (class "Default")
      (node (ref "C14") (pin "1") (pinfunction "1_1") (pintype "passive"))
      (node (ref "C15") (pin "1") (pinfunction "1_1") (pintype "passive"))
      (node (ref "C22") (pin "2") (pinfunction "2_2") (pintype "passive"))
      (node (ref "C23") (pin "2") (pinfunction "2_2") (pintype "passive"))
      (node (ref "C24") (pin "1") (pinfunction "1_1") (pintype "passive"))
      (node (ref "C25") (pin "1") (pinfunction "1_1") (pintype "passive"))
      (node (ref "C37") (pin "1") (pinfunction "1_1") (pintype "passive"))
      (node (ref "J2") (pin "1") (pinfunction "1_1") (pintype "passive"))
      (node (ref "L5") (pin "2") (pinfunction "2_2") (pintype "passive"))
      (node (ref "POWER") (pin "2") (pinfunction "2_2") (pintype "passive"))
      (node (ref "Psd") (pin "4") (pinfunction "4_4") (pintype "passive"))
      (node (ref "R1") (pin "2") (pinfunction "2_2") (pintype "passive"))
      (node (ref "R15") (pin "2") (pinfunction "2_2") (pintype "passive"))
      (node (ref "R16") (pin "2") (pinfunction "2_2") (pintype "passive"))
      (node (ref "R17") (pin "2") (pinfunction "2_2") (pintype "passive"))
      (node (ref "R18") (pin "2") (pinfunction "2_2") (pintype "passive"))
      (node (ref "R2") (pin "2") (pinfunction "2_2") (pintype "passive"))
      (node (ref "R23") (pin "2") (pinfunction "2_2") (pintype "passive"))
      (node (ref "R4") (pin "1") (pinfunction "1_1") (pintype "passive"))
      (node (ref "U3") (pin "2") (pinfunction "OUT_2") (pintype "output"))
      (node (ref "U4") (pin "1") (pinfunction "VBAT_1") (pintype "passive"))
      (node (ref "U4") (pin "19") (pinfunction "VDD_19") (pintype "passive"))
      (node (ref "U4") (pin "32") (pinfunction "VDD_32") (pintype "passive"))
      (node (ref "U4") (pin "48") (pinfunction "VDD_48") (pintype "passive"))
      (node (ref "U4") (pin "64") (pinfunction "VDD_64") (pintype "passive"))
      (node (ref "U5") (pin "15") (pinfunction "Vddtx_15") (pintype "passive"))
      (node (ref "U5") (pin "19") (pinfunction "Vddrx_19") (pintype "passive"))
      (node (ref "U5") (pin "20") (pinfunction "Vddpll_20") (pintype "passive"))
      (node (ref "U5") (pin "25") (pinfunction "Vddosc_25") (pintype "passive"))
      (node (ref "U5") (pin "28") (pinfunction "Vdd_28") (pintype "passive"))
      (node (ref "U6") (pin "16") (pinfunction "VCC_16") (pintype "power_in"))
      (node (ref "U7") (pin "12") (pinfunction "TTL_12") (pintype "passive"))
      (node (ref "U8") (pin "4") (pinfunction "VDD_4") (pintype "passive"))
      (node (ref "U9") (pin "8") (pinfunction "VCC_8") (pintype "power_in"))
    )
    (net (code "82") (name "V_5V") (class "Default")
      (node (ref "C12") (pin "1") (pinfunction "1_1") (pintype "passive"))
      (node (ref "C13") (pin "1") (pinfunction "1_1") (pintype "passive"))
      (node (ref "C2") (pin "1") (pinfunction "1_1") (pintype "passive"))
      (node (ref "L1") (pin "2") (pinfunction "2_2") (pintype "passive"))
      (node (ref "POWER") (pin "1") (pinfunction "1_1") (pintype "passive"))
      (node (ref "U1") (pin "4") (pinfunction "FB_4") (pintype "input"))
      (node (ref "U3") (pin "3") (pinfunction "IN_3") (pintype "input"))
    )
    (net (code "83") (name "V_12V") (class "Default")
      (node (ref "C1") (pin "1") (pinfunction "1_1") (pintype "passive"))
      (node (ref "C6") (pin "1") (pinfunction "1_1") (pintype "passive"))
      (node (ref "D1") (pin "2") (pinfunction "K_2") (pintype "passive"))
      (node (ref "P485") (pin "2") (pinfunction "2_2") (pintype "passive"))
      (node (ref "R0") (pin "2") (pinfunction "2_2") (pintype "passive"))
      (node (ref "U1") (pin "1") (pinfunction "IN_1") (pintype "power_in"))
      (node (ref "U2") (pin "1") (pinfunction "IN_1") (pintype "power_in"))
    )
    (net (code "84") (name "V_SIM") (class "Default")
      (node (ref "C3") (pin "1") (pinfunction "1_1") (pintype "passive"))
      (node (ref "C4") (pin "1") (pinfunction "1_1") (pintype "passive"))
      (node (ref "C5") (pin "1") (pinfunction "1_1") (pintype "passive"))
      (node (ref "C7") (pin "1") (pinfunction "1_1") (pintype "passive"))
      (node (ref "C8") (pin "1") (pinfunction "1_1") (pintype "passive"))
      (node (ref "C9") (pin "1") (pinfunction "1_1") (pintype "passive"))
      (node (ref "L3") (pin "2") (pinfunction "2_2") (pintype "passive"))
      (node (ref "U10") (pin "13") (pinfunction "VIN_13") (pintype "passive"))
      (node (ref "U10") (pin "14") (pinfunction "VIN_14") (pintype "passive"))
      (node (ref "U2") (pin "4") (pinfunction "FB_4") (pintype "input"))
      (node (ref "U7") (pin "1") (pinfunction "VCC_1") (pintype "passive"))
    )
    (net (code "85") (name "unconnected-(J1-MH1-Pad10)") (class "Default")
      (node (ref "J1") (pin "10") (pinfunction "MH1_10") (pintype "passive"))
    )
    (net (code "86") (name "unconnected-(J1-MH2-Pad11)") (class "Default")
      (node (ref "J1") (pin "11") (pinfunction "MH2_11") (pintype "passive"))
    )
    (net (code "87") (name "unconnected-(J1-Pad1)") (class "Default")
      (node (ref "J1") (pin "1") (pinfunction "1_1") (pintype "passive"))
    )
    (net (code "88") (name "unconnected-(J1-Pad4)") (class "Default")
      (node (ref "J1") (pin "4") (pinfunction "4_4") (pintype "passive"))
    )
    (net (code "89") (name "unconnected-(J1-Pad6)") (class "Default")
      (node (ref "J1") (pin "6") (pinfunction "6_6") (pintype "passive"))
    )
    (net (code "90") (name "unconnected-(J1-Pad7)") (class "Default")
      (node (ref "J1") (pin "7") (pinfunction "7_7") (pintype "passive"))
    )
    (net (code "91") (name "unconnected-(J1-Pad8)") (class "Default")
      (node (ref "J1") (pin "8") (pinfunction "8_8") (pintype "passive"))
    )
    (net (code "92") (name "unconnected-(J1-Pad9)") (class "Default")
      (node (ref "J1") (pin "9") (pinfunction "9_9") (pintype "passive"))
    )
    (net (code "93") (name "unconnected-(J3-MH1-Pad10)") (class "Default")
      (node (ref "J3") (pin "10") (pinfunction "MH1_10") (pintype "passive"))
    )
    (net (code "94") (name "unconnected-(J3-MH2-Pad11)") (class "Default")
      (node (ref "J3") (pin "11") (pinfunction "MH2_11") (pintype "passive"))
    )
    (net (code "95") (name "unconnected-(J3-Pad1)") (class "Default")
      (node (ref "J3") (pin "1") (pinfunction "1_1") (pintype "passive"))
    )
    (net (code "96") (name "unconnected-(J3-Pad4)") (class "Default")
      (node (ref "J3") (pin "4") (pinfunction "4_4") (pintype "passive"))
    )
    (net (code "97") (name "unconnected-(J3-Pad6)") (class "Default")
      (node (ref "J3") (pin "6") (pinfunction "6_6") (pintype "passive"))
    )
    (net (code "98") (name "unconnected-(J3-Pad7)") (class "Default")
      (node (ref "J3") (pin "7") (pinfunction "7_7") (pintype "passive"))
    )
    (net (code "99") (name "unconnected-(J3-Pad8)") (class "Default")
      (node (ref "J3") (pin "8") (pinfunction "8_8") (pintype "passive"))
    )
    (net (code "100") (name "unconnected-(J3-Pad9)") (class "Default")
      (node (ref "J3") (pin "9") (pinfunction "9_9") (pintype "passive"))
    )
    (net (code "101") (name "unconnected-(Psd-Pad8)") (class "Default")
      (node (ref "Psd") (pin "8") (pinfunction "8_8") (pintype "passive"))
    )
    (net (code "102") (name "unconnected-(Psd-Pad9)") (class "Default")
      (node (ref "Psd") (pin "9") (pinfunction "9_9") (pintype "passive"))
    )
    (net (code "103") (name "unconnected-(U4-PA8{slash}TIM1_CH1{slash}MCO-Pad41)") (class "Default")
      (node (ref "U4") (pin "41") (pinfunction "PA8/TIM1_CH1/MCO_41") (pintype "passive"))
    )
    (net (code "104") (name "unconnected-(U4-PA11{slash}CAN_RX{slash}USBDM{slash}TIM1_CH4-Pad44)") (class "Default")
      (node (ref "U4") (pin "44") (pinfunction "PA11/CAN_RX/USBDM/TIM1_CH4_44") (pintype "passive"))
    )
    (net (code "105") (name "unconnected-(U4-PA12{slash}CAN_TX{slash}USBDP{slash}TIM1_ETR-Pad45)") (class "Default")
      (node (ref "U4") (pin "45") (pinfunction "PA12/CAN_TX/USBDP/TIM1_ETR_45") (pintype "passive"))
    )
    (net (code "106") (name "unconnected-(U4-PA15{slash}JTDI{slash}SPI3_NSS{slash}I2S3_WS-Pad50)") (class "Default")
      (node (ref "U4") (pin "50") (pinfunction "PA15/JTDI/SPI3_NSS/I2S3_WS_50") (pintype "passive"))
    )
    (net (code "107") (name "unconnected-(U4-PB3{slash}JTDO{slash}SPI3_SCK{slash}I2S3_CK-Pad55)") (class "Default")
      (node (ref "U4") (pin "55") (pinfunction "PB3/JTDO/SPI3_SCK/I2S3_CK_55") (pintype "passive"))
    )
    (net (code "108") (name "unconnected-(U4-PB4{slash}JNTRST{slash}SPI3_MISO-Pad56)") (class "Default")
      (node (ref "U4") (pin "56") (pinfunction "PB4/JNTRST/SPI3_MISO_56") (pintype "passive"))
    )
    (net (code "109") (name "unconnected-(U4-PB5{slash}I2C1_SMBA{slash}SPI3_MOSI{slash}I2S3_SD-Pad57)") (class "Default")
      (node (ref "U4") (pin "57") (pinfunction "PB5/I2C1_SMBA/SPI3_MOSI/I2S3_SD_57") (pintype "passive"))
    )
    (net (code "110") (name "unconnected-(U4-PB6{slash}I2C1_SCL{slash}TIM4_CH1-Pad58)") (class "Default")
      (node (ref "U4") (pin "58") (pinfunction "PB6/I2C1_SCL/TIM4_CH1_58") (pintype "passive"))
    )
    (net (code "111") (name "unconnected-(U4-PB7{slash}I2C1_SDA{slash}TIM4_CH2-Pad59)") (class "Default")
      (node (ref "U4") (pin "59") (pinfunction "PB7/I2C1_SDA/TIM4_CH2_59") (pintype "passive"))
    )
    (net (code "112") (name "unconnected-(U4-PB8{slash}TIM4_CH3{slash}SDIO_D4-Pad61)") (class "Default")
      (node (ref "U4") (pin "61") (pinfunction "PB8/TIM4_CH3/SDIO_D4_61") (pintype "passive"))
    )
    (net (code "113") (name "unconnected-(U4-PB9{slash}TIM4_CH4{slash}SDIO_D5-Pad62)") (class "Default")
      (node (ref "U4") (pin "62") (pinfunction "PB9/TIM4_CH4/SDIO_D5_62") (pintype "passive"))
    )
    (net (code "114") (name "unconnected-(U4-PC8{slash}TIM8_CH3{slash}SDIO_D0-Pad39)") (class "Default")
      (node (ref "U4") (pin "39") (pinfunction "PC8/TIM8_CH3/SDIO_D0_39") (pintype "passive"))
    )
    (net (code "115") (name "unconnected-(U4-PC9{slash}TIM8_CH4{slash}SDIO_D1-Pad40)") (class "Default")
      (node (ref "U4") (pin "40") (pinfunction "PC9/TIM8_CH4/SDIO_D1_40") (pintype "passive"))
    )
    (net (code "116") (name "unconnected-(U5-CLKOUT-Pad3)") (class "Default")
      (node (ref "U5") (pin "3") (pinfunction "CLKOUT_3") (pintype "passive"))
    )
    (net (code "117") (name "unconnected-(U5-~{WOL}-Pad5)") (class "Default")
      (node (ref "U5") (pin "5") (pinfunction "~{WOL}_5") (pintype "passive"))
    )
    (net (code "118") (name "unconnected-(U7-DTR-Pad7)") (class "Default")
      (node (ref "U7") (pin "7") (pinfunction "DTR_7") (pintype "passive"))
    )
    (net (code "119") (name "unconnected-(U7-M+-Pad10)") (class "Default")
      (node (ref "U7") (pin "10") (pinfunction "M+_10") (pintype "passive"))
    )
    (net (code "120") (name "unconnected-(U7-M--Pad11)") (class "Default")
      (node (ref "U7") (pin "11") (pinfunction "M-_11") (pintype "passive"))
    )
    (net (code "121") (name "unconnected-(U7-NET-Pad14)") (class "Default")
      (node (ref "U7") (pin "14") (pinfunction "NET_14") (pintype "passive"))
    )
    (net (code "122") (name "unconnected-(U7-PWK-Pad5)") (class "Default")
      (node (ref "U7") (pin "5") (pinfunction "PWK_5") (pintype "passive"))
    )
    (net (code "123") (name "unconnected-(U7-RI-Pad6)") (class "Default")
      (node (ref "U7") (pin "6") (pinfunction "RI_6") (pintype "passive"))
    )
    (net (code "124") (name "unconnected-(U7-RTC-Pad13)") (class "Default")
      (node (ref "U7") (pin "13") (pinfunction "RTC_13") (pintype "passive"))
    )
    (net (code "125") (name "unconnected-(U7-S+-Pad8)") (class "Default")
      (node (ref "U7") (pin "8") (pinfunction "S+_8") (pintype "passive"))
    )
    (net (code "126") (name "unconnected-(U7-S--Pad9)") (class "Default")
      (node (ref "U7") (pin "9") (pinfunction "S-_9") (pintype "passive"))
    )
    (net (code "127") (name "unconnected-(U8-CD-Pad10)") (class "Default")
      (node (ref "U8") (pin "10") (pinfunction "CD_10") (pintype "passive"))
    )
    (net (code "128") (name "unconnected-(U8-DATA1-Pad8)") (class "Default")
      (node (ref "U8") (pin "8") (pinfunction "DATA1_8") (pintype "passive"))
    )
    (net (code "129") (name "unconnected-(U8-DATA2-Pad9)") (class "Default")
      (node (ref "U8") (pin "9") (pinfunction "DATA2_9") (pintype "passive"))
    )
    (net (code "130") (name "unconnected-(U8-GND-Pad11)") (class "Default")
      (node (ref "U8") (pin "11") (pinfunction "GND_11") (pintype "passive"))
    )
    (net (code "131") (name "unconnected-(U8-WP-Pad12)") (class "Default")
      (node (ref "U8") (pin "12") (pinfunction "WP_12") (pintype "passive"))
    )
    (net (code "132") (name "unconnected-(U10-LED_NET-Pad15)") (class "Default")
      (node (ref "U10") (pin "15") (pinfunction "LED_NET_15") (pintype "passive"))
    )
    (net (code "133") (name "unconnected-(U10-LED_WORK-Pad9)") (class "Default")
      (node (ref "U10") (pin "9") (pinfunction "LED_WORK_9") (pintype "passive"))
    )
    (net (code "134") (name "unconnected-(U10-LINKA-Pad1)") (class "Default")
      (node (ref "U10") (pin "1") (pinfunction "LINKA_1") (pintype "passive"))
    )
    (net (code "135") (name "unconnected-(U10-LINKB-Pad2)") (class "Default")
      (node (ref "U10") (pin "2") (pinfunction "LINKB_2") (pintype "passive"))
    )
    (net (code "136") (name "unconnected-(U10-NC1-Pad8)") (class "Default")
      (node (ref "U10") (pin "8") (pinfunction "NC1_8") (pintype "passive"))
    )
    (net (code "137") (name "unconnected-(U10-NC2-Pad17)") (class "Default")
      (node (ref "U10") (pin "17") (pinfunction "NC2_17") (pintype "passive"))
    )
    (net (code "138") (name "unconnected-(U10-RESET-Pad19)") (class "Default")
      (node (ref "U10") (pin "19") (pinfunction "RESET_19") (pintype "passive"))
    )
    (net (code "139") (name "unconnected-(U10-Reload-Pad18)") (class "Default")
      (node (ref "U10") (pin "18") (pinfunction "Reload_18") (pintype "passive"))
    )
    (net (code "140") (name "unconnected-(U10-USB_D+-Pad4)") (class "Default")
      (node (ref "U10") (pin "4") (pinfunction "USB_D+_4") (pintype "passive"))
    )
    (net (code "141") (name "unconnected-(U10-USB_D--Pad3)") (class "Default")
      (node (ref "U10") (pin "3") (pinfunction "USB_D-_3") (pintype "passive"))
    )
    (net (code "142") (name "unconnected-(U10-VCAP-Pad16)") (class "Default")
      (node (ref "U10") (pin "16") (pinfunction "VCAP_16") (pintype "passive"))
    )
    (net (code "143") (name "unconnected-(U10-VCC_IO-Pad5)") (class "Default")
      (node (ref "U10") (pin "5") (pinfunction "VCC_IO_5") (pintype "passive"))
    )
    (net (code "144") (name "unconnected-(U10-VSIM-Pad20)") (class "Default")
      (node (ref "U10") (pin "20") (pinfunction "VSIM_20") (pintype "passive"))
    )
    (net (code "145") (name "unconnected-(U10-VSIM_CLK-Pad22)") (class "Default")
      (node (ref "U10") (pin "22") (pinfunction "VSIM_CLK_22") (pintype "passive"))
    )
    (net (code "146") (name "unconnected-(U10-VSIM_DATA-Pad21)") (class "Default")
      (node (ref "U10") (pin "21") (pinfunction "VSIM_DATA_21") (pintype "passive"))
    )
    (net (code "147") (name "unconnected-(U10-VSIM_RST-Pad23)") (class "Default")
      (node (ref "U10") (pin "23") (pinfunction "VSIM_RST_23") (pintype "passive"))
    )
    (net (code "148") (name "unconnected-(WAN1-Pad8)") (class "Default")
      (node (ref "WAN1") (pin "8") (pintype "passive"))
    )
  )
)
